# FPGA_7A35T_GTP.net
KiCad netlist of a schematic drawn in Altium Designer
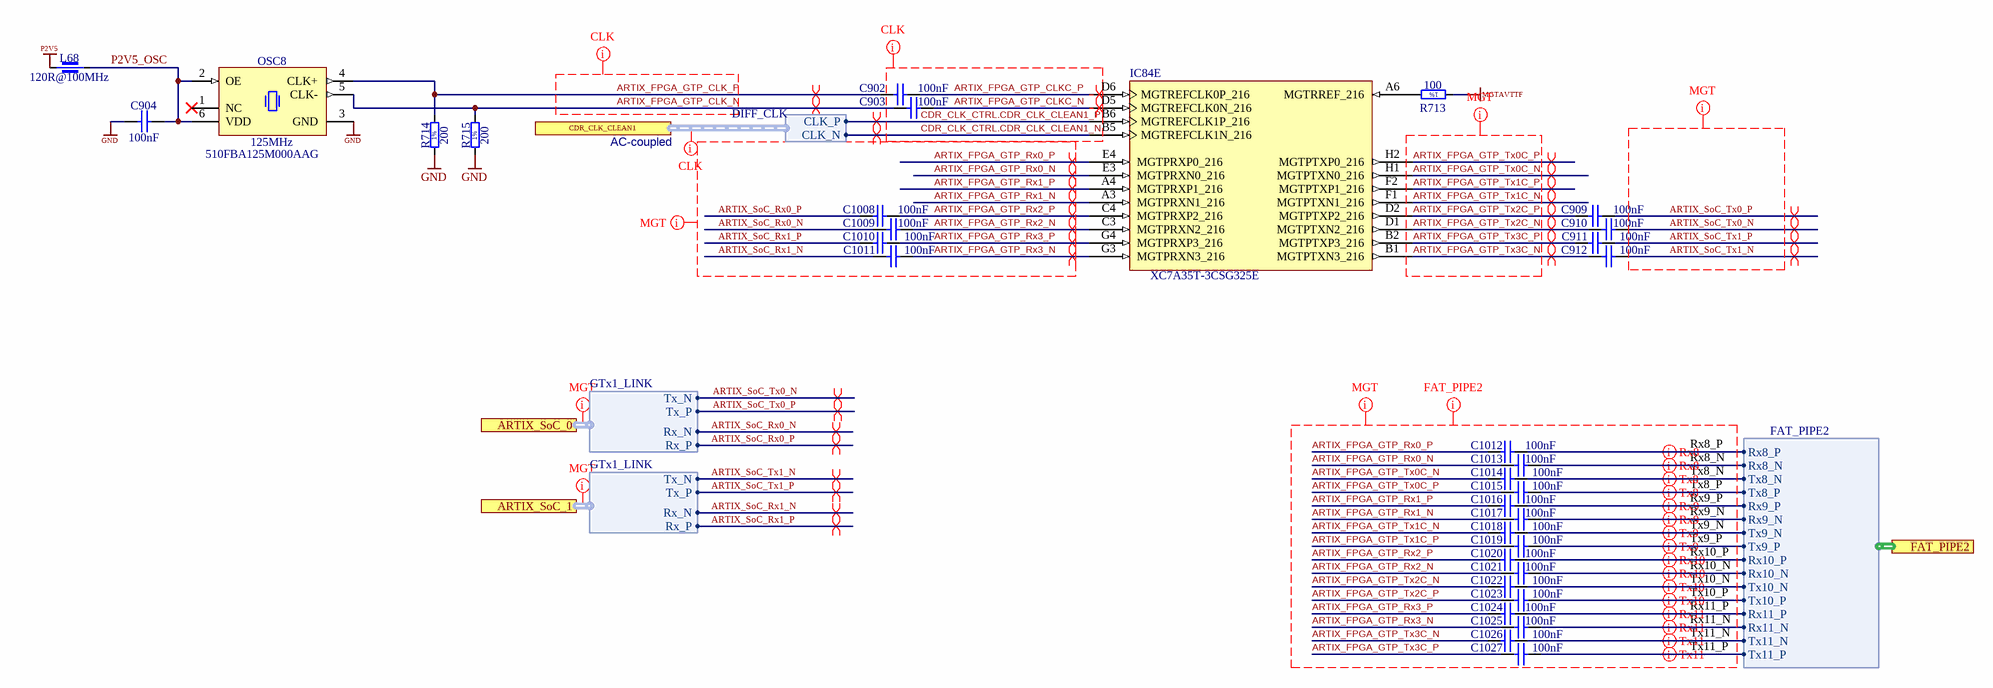
[diagram p0: FPGA_7A35T_GTP.SchDoc]

(export (version "E")
  (design (tool "Eeschema 10.0.6"))
  (components
    (comp (ref "C902")
      (value "100nF")
      (footprint "CAPC0603X33N")
      (description "Non-polarised capacitor")
      (fields
        (field (name "MANUFACTURER PART NUMBER") "CC0201_100NF_6.3V_10%_X5R")
        (field (name "MANUFACTURER") "GENERIC")
        (field (name "AUTHOR") "CERN DEM JLC")
      )
      (libsource (lib "Capacitors") (part "Capacitor - non polarized"))
    )
    (comp (ref "C903")
      (value "100nF")
      (footprint "CAPC0603X33N")
      (description "Non-polarised capacitor")
      (fields
        (field (name "MANUFACTURER PART NUMBER") "CC0201_100NF_6.3V_10%_X5R")
        (field (name "MANUFACTURER") "GENERIC")
        (field (name "AUTHOR") "CERN DEM JLC")
      )
      (libsource (lib "Capacitors") (part "Capacitor - non polarized"))
    )
    (comp (ref "C904")
      (value "100nF")
      (footprint "CAPC0603X33N")
      (description "Non-polarised capacitor")
      (fields
        (field (name "MANUFACTURER PART NUMBER") "CC0201_100NF_6.3V_10%_X5R")
        (field (name "MANUFACTURER") "GENERIC")
        (field (name "AUTHOR") "CERN DEM JLC")
      )
      (libsource (lib "Capacitors") (part "Capacitor - non polarized"))
    )
    (comp (ref "C909")
      (value "100nF")
      (footprint "CAPC0603X33N")
      (description "Non-polarised capacitor")
      (fields
        (field (name "MANUFACTURER PART NUMBER") "CC0201_100NF_6.3V_10%_X5R")
        (field (name "MANUFACTURER") "GENERIC")
        (field (name "AUTHOR") "CERN DEM JLC")
      )
      (libsource (lib "Capacitors") (part "Capacitor - non polarized"))
    )
    (comp (ref "C910")
      (value "100nF")
      (footprint "CAPC0603X33N")
      (description "Non-polarised capacitor")
      (fields
        (field (name "MANUFACTURER PART NUMBER") "CC0201_100NF_6.3V_10%_X5R")
        (field (name "MANUFACTURER") "GENERIC")
        (field (name "AUTHOR") "CERN DEM JLC")
      )
      (libsource (lib "Capacitors") (part "Capacitor - non polarized"))
    )
    (comp (ref "C911")
      (value "100nF")
      (footprint "CAPC0603X33N")
      (description "Non-polarised capacitor")
      (fields
        (field (name "MANUFACTURER PART NUMBER") "CC0201_100NF_6.3V_10%_X5R")
        (field (name "MANUFACTURER") "GENERIC")
        (field (name "AUTHOR") "CERN DEM JLC")
      )
      (libsource (lib "Capacitors") (part "Capacitor - non polarized"))
    )
    (comp (ref "C912")
      (value "100nF")
      (footprint "CAPC0603X33N")
      (description "Non-polarised capacitor")
      (fields
        (field (name "MANUFACTURER PART NUMBER") "CC0201_100NF_6.3V_10%_X5R")
        (field (name "MANUFACTURER") "GENERIC")
        (field (name "AUTHOR") "CERN DEM JLC")
      )
      (libsource (lib "Capacitors") (part "Capacitor - non polarized"))
    )
    (comp (ref "C1008")
      (value "100nF")
      (footprint "CAPC0603X33N")
      (description "Non-polarised capacitor")
      (fields
        (field (name "MANUFACTURER PART NUMBER") "CC0201_100NF_6.3V_10%_X5R")
        (field (name "MANUFACTURER") "GENERIC")
        (field (name "AUTHOR") "CERN DEM JLC")
      )
      (libsource (lib "Capacitors") (part "Capacitor - non polarized"))
    )
    (comp (ref "C1009")
      (value "100nF")
      (footprint "CAPC0603X33N")
      (description "Non-polarised capacitor")
      (fields
        (field (name "MANUFACTURER PART NUMBER") "CC0201_100NF_6.3V_10%_X5R")
        (field (name "MANUFACTURER") "GENERIC")
        (field (name "AUTHOR") "CERN DEM JLC")
      )
      (libsource (lib "Capacitors") (part "Capacitor - non polarized"))
    )
    (comp (ref "C1010")
      (value "100nF")
      (footprint "CAPC0603X33N")
      (description "Non-polarised capacitor")
      (fields
        (field (name "MANUFACTURER PART NUMBER") "CC0201_100NF_6.3V_10%_X5R")
        (field (name "MANUFACTURER") "GENERIC")
        (field (name "AUTHOR") "CERN DEM JLC")
      )
      (libsource (lib "Capacitors") (part "Capacitor - non polarized"))
    )
    (comp (ref "C1011")
      (value "100nF")
      (footprint "CAPC0603X33N")
      (description "Non-polarised capacitor")
      (fields
        (field (name "MANUFACTURER PART NUMBER") "CC0201_100NF_6.3V_10%_X5R")
        (field (name "MANUFACTURER") "GENERIC")
        (field (name "AUTHOR") "CERN DEM JLC")
      )
      (libsource (lib "Capacitors") (part "Capacitor - non polarized"))
    )
    (comp (ref "C1012")
      (value "100nF")
      (footprint "CAPC0603X33N")
      (description "Non-polarised capacitor")
      (fields
        (field (name "MANUFACTURER PART NUMBER") "CC0201_100NF_6.3V_10%_X5R")
        (field (name "MANUFACTURER") "GENERIC")
        (field (name "AUTHOR") "CERN DEM JLC")
      )
      (libsource (lib "Capacitors") (part "Capacitor - non polarized"))
    )
    (comp (ref "C1013")
      (value "100nF")
      (footprint "CAPC0603X33N")
      (description "Non-polarised capacitor")
      (fields
        (field (name "MANUFACTURER PART NUMBER") "CC0201_100NF_6.3V_10%_X5R")
        (field (name "MANUFACTURER") "GENERIC")
        (field (name "AUTHOR") "CERN DEM JLC")
      )
      (libsource (lib "Capacitors") (part "Capacitor - non polarized"))
    )
    (comp (ref "C1014")
      (value "100nF")
      (footprint "CAPC0603X33N")
      (description "Non-polarised capacitor")
      (fields
        (field (name "MANUFACTURER PART NUMBER") "CC0201_100NF_6.3V_10%_X5R")
        (field (name "MANUFACTURER") "GENERIC")
        (field (name "AUTHOR") "CERN DEM JLC")
      )
      (libsource (lib "Capacitors") (part "Capacitor - non polarized"))
    )
    (comp (ref "C1015")
      (value "100nF")
      (footprint "CAPC0603X33N")
      (description "Non-polarised capacitor")
      (fields
        (field (name "MANUFACTURER PART NUMBER") "CC0201_100NF_6.3V_10%_X5R")
        (field (name "MANUFACTURER") "GENERIC")
        (field (name "AUTHOR") "CERN DEM JLC")
      )
      (libsource (lib "Capacitors") (part "Capacitor - non polarized"))
    )
    (comp (ref "C1016")
      (value "100nF")
      (footprint "CAPC0603X33N")
      (description "Non-polarised capacitor")
      (fields
        (field (name "MANUFACTURER PART NUMBER") "CC0201_100NF_6.3V_10%_X5R")
        (field (name "MANUFACTURER") "GENERIC")
        (field (name "AUTHOR") "CERN DEM JLC")
      )
      (libsource (lib "Capacitors") (part "Capacitor - non polarized"))
    )
    (comp (ref "C1017")
      (value "100nF")
      (footprint "CAPC0603X33N")
      (description "Non-polarised capacitor")
      (fields
        (field (name "MANUFACTURER PART NUMBER") "CC0201_100NF_6.3V_10%_X5R")
        (field (name "MANUFACTURER") "GENERIC")
        (field (name "AUTHOR") "CERN DEM JLC")
      )
      (libsource (lib "Capacitors") (part "Capacitor - non polarized"))
    )
    (comp (ref "C1018")
      (value "100nF")
      (footprint "CAPC0603X33N")
      (description "Non-polarised capacitor")
      (fields
        (field (name "MANUFACTURER PART NUMBER") "CC0201_100NF_6.3V_10%_X5R")
        (field (name "MANUFACTURER") "GENERIC")
        (field (name "AUTHOR") "CERN DEM JLC")
      )
      (libsource (lib "Capacitors") (part "Capacitor - non polarized"))
    )
    (comp (ref "C1019")
      (value "100nF")
      (footprint "CAPC0603X33N")
      (description "Non-polarised capacitor")
      (fields
        (field (name "MANUFACTURER PART NUMBER") "CC0201_100NF_6.3V_10%_X5R")
        (field (name "MANUFACTURER") "GENERIC")
        (field (name "AUTHOR") "CERN DEM JLC")
      )
      (libsource (lib "Capacitors") (part "Capacitor - non polarized"))
    )
    (comp (ref "C1020")
      (value "100nF")
      (footprint "CAPC0603X33N")
      (description "Non-polarised capacitor")
      (fields
        (field (name "MANUFACTURER PART NUMBER") "CC0201_100NF_6.3V_10%_X5R")
        (field (name "MANUFACTURER") "GENERIC")
        (field (name "AUTHOR") "CERN DEM JLC")
      )
      (libsource (lib "Capacitors") (part "Capacitor - non polarized"))
    )
    (comp (ref "C1021")
      (value "100nF")
      (footprint "CAPC0603X33N")
      (description "Non-polarised capacitor")
      (fields
        (field (name "MANUFACTURER PART NUMBER") "CC0201_100NF_6.3V_10%_X5R")
        (field (name "MANUFACTURER") "GENERIC")
        (field (name "AUTHOR") "CERN DEM JLC")
      )
      (libsource (lib "Capacitors") (part "Capacitor - non polarized"))
    )
    (comp (ref "C1022")
      (value "100nF")
      (footprint "CAPC0603X33N")
      (description "Non-polarised capacitor")
      (fields
        (field (name "MANUFACTURER PART NUMBER") "CC0201_100NF_6.3V_10%_X5R")
        (field (name "MANUFACTURER") "GENERIC")
        (field (name "AUTHOR") "CERN DEM JLC")
      )
      (libsource (lib "Capacitors") (part "Capacitor - non polarized"))
    )
    (comp (ref "C1023")
      (value "100nF")
      (footprint "CAPC0603X33N")
      (description "Non-polarised capacitor")
      (fields
        (field (name "MANUFACTURER PART NUMBER") "CC0201_100NF_6.3V_10%_X5R")
        (field (name "MANUFACTURER") "GENERIC")
        (field (name "AUTHOR") "CERN DEM JLC")
      )
      (libsource (lib "Capacitors") (part "Capacitor - non polarized"))
    )
    (comp (ref "C1024")
      (value "100nF")
      (footprint "CAPC0603X33N")
      (description "Non-polarised capacitor")
      (fields
        (field (name "MANUFACTURER PART NUMBER") "CC0201_100NF_6.3V_10%_X5R")
        (field (name "MANUFACTURER") "GENERIC")
        (field (name "AUTHOR") "CERN DEM JLC")
      )
      (libsource (lib "Capacitors") (part "Capacitor - non polarized"))
    )
    (comp (ref "C1025")
      (value "100nF")
      (footprint "CAPC0603X33N")
      (description "Non-polarised capacitor")
      (fields
        (field (name "MANUFACTURER PART NUMBER") "CC0201_100NF_6.3V_10%_X5R")
        (field (name "MANUFACTURER") "GENERIC")
        (field (name "AUTHOR") "CERN DEM JLC")
      )
      (libsource (lib "Capacitors") (part "Capacitor - non polarized"))
    )
    (comp (ref "C1026")
      (value "100nF")
      (footprint "CAPC0603X33N")
      (description "Non-polarised capacitor")
      (fields
        (field (name "MANUFACTURER PART NUMBER") "CC0201_100NF_6.3V_10%_X5R")
        (field (name "MANUFACTURER") "GENERIC")
        (field (name "AUTHOR") "CERN DEM JLC")
      )
      (libsource (lib "Capacitors") (part "Capacitor - non polarized"))
    )
    (comp (ref "C1027")
      (value "100nF")
      (footprint "CAPC0603X33N")
      (description "Non-polarised capacitor")
      (fields
        (field (name "MANUFACTURER PART NUMBER") "CC0201_100NF_6.3V_10%_X5R")
        (field (name "MANUFACTURER") "GENERIC")
        (field (name "AUTHOR") "CERN DEM JLC")
      )
      (libsource (lib "Capacitors") (part "Capacitor - non polarized"))
    )
    (comp (ref "IC84")
      (value "XC7A35T-3CSG325E")
      (footprint "CSG325")
      (description "Artix-7 FPGA, 150 User I/Os, 4 GTP, 324-Ball BGA, Speed Grade 3, Extended Grade, Pb-Free")
      (fields (field (name "MANUFACTURER") "Xilinx"))
      (libsource (lib "Altium Content Vault") (part "XLNX-XC7A35T-CSG325"))
    )
    (comp (ref "L68")
      (value "120R@100MHz")
      (footprint "INDC1005X55N")
      (fields
        (field (name "MANUFACTURER PART NUMBER") "BLM15PX121SN1D")
        (field (name "MANUFACTURER") "MURATA")
        (field (name "PART NUMBER") "IND0402_MURATA_BLM15PX121SN1D")
        (field (name "AUTHOR") "CERN DEM JMW")
      )
      (libsource (lib "Inductors & Transformers") (part "Ferrite Bead"))
    )
    (comp (ref "OSC8")
      (value "125MHz")
      (footprint "OSC_SILICON-LAB_SI510-6N(5X7)")
      (description "Crystal Oscillator 6 pins, Si510 (LVDS/LVPECL/HCSL/Dual CMOS)")
      (fields
        (field (name "PART NUMBER") "OSC_125MHZ_SILICON-LAB_510FBA125M000AAG")
        (field (name "MANUFACTURER") "SILICON LABS")
        (field (name "MANUFACTURER PART NUMBER") "510FBA125M000AAG")
        (field (name "AUTHOR") "CERN DEM JMW")
      )
      (libsource (lib "ICs And Semiconductors") (part "Oscillator SILICON-LAB_Si510-6N"))
    )
    (comp (ref "R713")
      (value "100")
      (footprint "RESC1005X40N")
      (description "Resistor - 1%")
      (fields
        (field (name "MANUFACTURER PART NUMBER") "R0402_100R_1%_0.0625W_100PPM")
        (field (name "MANUFACTURER") "GENERIC")
        (field (name "AUTHOR") "CERN DEM JLC")
      )
      (libsource (lib "Resistors") (part "Resistor - 1%"))
    )
    (comp (ref "R714")
      (value "200")
      (footprint "RESC1005X40N")
      (description "Resistor - 1%")
      (fields
        (field (name "MANUFACTURER PART NUMBER") "R0402_200R_1%_0.0625W_100PPM")
        (field (name "MANUFACTURER") "GENERIC")
        (field (name "AUTHOR") "CERN DEM JLC")
      )
      (libsource (lib "Resistors") (part "Resistor - 1%"))
    )
    (comp (ref "R715")
      (value "200")
      (footprint "RESC1005X40N")
      (description "Resistor - 1%")
      (fields
        (field (name "MANUFACTURER PART NUMBER") "R0402_200R_1%_0.0625W_100PPM")
        (field (name "MANUFACTURER") "GENERIC")
        (field (name "AUTHOR") "CERN DEM JLC")
      )
      (libsource (lib "Resistors") (part "Resistor - 1%"))
    )
  )
  (nets
    (net (code "4") (name "/ARTIX_FPGA_GTP_CLKC_N") (class "Default")
      (node (ref "C903") (pin "2") (pinfunction "2_2") (pintype "passive"))
      (node (ref "IC84") (pin "D5") (pinfunction "MGTREFCLK0N_216_D5") (pintype "input"))
    )
    (net (code "5") (name "/ARTIX_FPGA_GTP_CLKC_P") (class "Default")
      (node (ref "C902") (pin "2") (pinfunction "2_2") (pintype "passive"))
      (node (ref "IC84") (pin "D6") (pinfunction "MGTREFCLK0P_216_D6") (pintype "input"))
    )
    (net (code "6") (name "/ARTIX_FPGA_GTP_CLK_N") (class "Default")
      (node (ref "C903") (pin "1") (pinfunction "1_1") (pintype "passive"))
      (node (ref "OSC8") (pin "5") (pinfunction "CLK-_5") (pintype "output"))
      (node (ref "R715") (pin "2") (pinfunction "2_2") (pintype "passive"))
    )
    (net (code "7") (name "/ARTIX_FPGA_GTP_CLK_P") (class "Default")
      (node (ref "C902") (pin "1") (pinfunction "1_1") (pintype "passive"))
      (node (ref "OSC8") (pin "4") (pinfunction "CLK+_4") (pintype "output"))
      (node (ref "R714") (pin "2") (pinfunction "2_2") (pintype "passive"))
    )
    (net (code "8") (name "/ARTIX_FPGA_GTP_Rx0_N") (class "Default")
      (node (ref "C1013") (pin "2") (pinfunction "2_2") (pintype "passive"))
      (node (ref "IC84") (pin "E3") (pinfunction "MGTPRXN0_216_E3") (pintype "input"))
    )
    (net (code "9") (name "/ARTIX_FPGA_GTP_Rx0_P") (class "Default")
      (node (ref "C1012") (pin "2") (pinfunction "2_2") (pintype "passive"))
      (node (ref "IC84") (pin "E4") (pinfunction "MGTPRXP0_216_E4") (pintype "input"))
    )
    (net (code "10") (name "/ARTIX_FPGA_GTP_Rx1_N") (class "Default")
      (node (ref "C1017") (pin "2") (pinfunction "2_2") (pintype "passive"))
      (node (ref "IC84") (pin "A3") (pinfunction "MGTPRXN1_216_A3") (pintype "input"))
    )
    (net (code "11") (name "/ARTIX_FPGA_GTP_Rx1_P") (class "Default")
      (node (ref "C1016") (pin "2") (pinfunction "2_2") (pintype "passive"))
      (node (ref "IC84") (pin "A4") (pinfunction "MGTPRXP1_216_A4") (pintype "input"))
    )
    (net (code "12") (name "/ARTIX_FPGA_GTP_Rx2_N") (class "Default")
      (node (ref "C1009") (pin "1") (pinfunction "1_1") (pintype "passive"))
      (node (ref "C1021") (pin "2") (pinfunction "2_2") (pintype "passive"))
      (node (ref "IC84") (pin "C3") (pinfunction "MGTPRXN2_216_C3") (pintype "input"))
    )
    (net (code "13") (name "/ARTIX_FPGA_GTP_Rx2_P") (class "Default")
      (node (ref "C1008") (pin "1") (pinfunction "1_1") (pintype "passive"))
      (node (ref "C1020") (pin "2") (pinfunction "2_2") (pintype "passive"))
      (node (ref "IC84") (pin "C4") (pinfunction "MGTPRXP2_216_C4") (pintype "input"))
    )
    (net (code "14") (name "/ARTIX_FPGA_GTP_Rx3_N") (class "Default")
      (node (ref "C1011") (pin "1") (pinfunction "1_1") (pintype "passive"))
      (node (ref "C1025") (pin "2") (pinfunction "2_2") (pintype "passive"))
      (node (ref "IC84") (pin "G3") (pinfunction "MGTPRXN3_216_G3") (pintype "input"))
    )
    (net (code "15") (name "/ARTIX_FPGA_GTP_Rx3_P") (class "Default")
      (node (ref "C1010") (pin "1") (pinfunction "1_1") (pintype "passive"))
      (node (ref "C1024") (pin "2") (pinfunction "2_2") (pintype "passive"))
      (node (ref "IC84") (pin "G4") (pinfunction "MGTPRXP3_216_G4") (pintype "input"))
    )
    (net (code "16") (name "/ARTIX_FPGA_GTP_Tx0C_N") (class "Default")
      (node (ref "C1014") (pin "2") (pinfunction "2_2") (pintype "passive"))
      (node (ref "IC84") (pin "H1") (pinfunction "MGTPTXN0_216_H1") (pintype "output"))
    )
    (net (code "17") (name "/ARTIX_FPGA_GTP_Tx0C_P") (class "Default")
      (node (ref "C1015") (pin "2") (pinfunction "2_2") (pintype "passive"))
      (node (ref "IC84") (pin "H2") (pinfunction "MGTPTXP0_216_H2") (pintype "output"))
    )
    (net (code "18") (name "/ARTIX_FPGA_GTP_Tx1C_N") (class "Default")
      (node (ref "C1018") (pin "2") (pinfunction "2_2") (pintype "passive"))
      (node (ref "IC84") (pin "F1") (pinfunction "MGTPTXN1_216_F1") (pintype "output"))
    )
    (net (code "19") (name "/ARTIX_FPGA_GTP_Tx1C_P") (class "Default")
      (node (ref "C1019") (pin "2") (pinfunction "2_2") (pintype "passive"))
      (node (ref "IC84") (pin "F2") (pinfunction "MGTPTXP1_216_F2") (pintype "output"))
    )
    (net (code "20") (name "/ARTIX_FPGA_GTP_Tx2C_N") (class "Default")
      (node (ref "C1022") (pin "2") (pinfunction "2_2") (pintype "passive"))
      (node (ref "C910") (pin "2") (pinfunction "2_2") (pintype "passive"))
      (node (ref "IC84") (pin "D1") (pinfunction "MGTPTXN2_216_D1") (pintype "output"))
    )
    (net (code "21") (name "/ARTIX_FPGA_GTP_Tx2C_P") (class "Default")
      (node (ref "C1023") (pin "2") (pinfunction "2_2") (pintype "passive"))
      (node (ref "C909") (pin "2") (pinfunction "2_2") (pintype "passive"))
      (node (ref "IC84") (pin "D2") (pinfunction "MGTPTXP2_216_D2") (pintype "output"))
    )
    (net (code "22") (name "/ARTIX_FPGA_GTP_Tx3C_N") (class "Default")
      (node (ref "C1026") (pin "2") (pinfunction "2_2") (pintype "passive"))
      (node (ref "C912") (pin "2") (pinfunction "2_2") (pintype "passive"))
      (node (ref "IC84") (pin "B1") (pinfunction "MGTPTXN3_216_B1") (pintype "output"))
    )
    (net (code "23") (name "/ARTIX_FPGA_GTP_Tx3C_P") (class "Default")
      (node (ref "C1027") (pin "2") (pinfunction "2_2") (pintype "passive"))
      (node (ref "C911") (pin "2") (pinfunction "2_2") (pintype "passive"))
      (node (ref "IC84") (pin "B2") (pinfunction "MGTPTXP3_216_B2") (pintype "output"))
    )
    (net (code "24") (name "/ARTIX_SoC_Rx0_N") (class "Default")
      (node (ref "C1009") (pin "2") (pinfunction "2_2") (pintype "passive"))
    )
    (net (code "25") (name "/ARTIX_SoC_Rx0_P") (class "Default")
      (node (ref "C1008") (pin "2") (pinfunction "2_2") (pintype "passive"))
    )
    (net (code "26") (name "/ARTIX_SoC_Rx1_N") (class "Default")
      (node (ref "C1011") (pin "2") (pinfunction "2_2") (pintype "passive"))
    )
    (net (code "27") (name "/ARTIX_SoC_Rx1_P") (class "Default")
      (node (ref "C1010") (pin "2") (pinfunction "2_2") (pintype "passive"))
    )
    (net (code "28") (name "/ARTIX_SoC_Tx0_N") (class "Default")
      (node (ref "C910") (pin "1") (pinfunction "1_1") (pintype "passive"))
    )
    (net (code "29") (name "/ARTIX_SoC_Tx0_P") (class "Default")
      (node (ref "C909") (pin "1") (pinfunction "1_1") (pintype "passive"))
    )
    (net (code "30") (name "/ARTIX_SoC_Tx1_N") (class "Default")
      (node (ref "C912") (pin "1") (pinfunction "1_1") (pintype "passive"))
    )
    (net (code "31") (name "/ARTIX_SoC_Tx1_P") (class "Default")
      (node (ref "C911") (pin "1") (pinfunction "1_1") (pintype "passive"))
    )
    (net (code "32") (name "/CDR_CLK_CTRL.CDR_CLK_CLEAN1_N") (class "Default")
      (node (ref "IC84") (pin "B5") (pinfunction "MGTREFCLK1N_216_B5") (pintype "input"))
    )
    (net (code "33") (name "/CDR_CLK_CTRL.CDR_CLK_CLEAN1_P") (class "Default")
      (node (ref "IC84") (pin "B6") (pinfunction "MGTREFCLK1P_216_B6") (pintype "input"))
    )
    (net (code "34") (name "/P2V5_OSC") (class "Default")
      (node (ref "C904") (pin "2") (pinfunction "2_2") (pintype "passive"))
      (node (ref "L68") (pin "1") (pinfunction "1_1") (pintype "passive"))
      (node (ref "OSC8") (pin "2") (pinfunction "OE_2") (pintype "input"))
      (node (ref "OSC8") (pin "6") (pinfunction "VDD_6") (pintype "power_in"))
    )
    (net (code "35") (name "/Rx8_N") (class "Default")
      (node (ref "C1013") (pin "1") (pinfunction "1_1") (pintype "passive"))
    )
    (net (code "36") (name "/Rx8_P") (class "Default")
      (node (ref "C1012") (pin "1") (pinfunction "1_1") (pintype "passive"))
    )
    (net (code "37") (name "/Rx9_N") (class "Default")
      (node (ref "C1017") (pin "1") (pinfunction "1_1") (pintype "passive"))
    )
    (net (code "38") (name "/Rx9_P") (class "Default")
      (node (ref "C1016") (pin "1") (pinfunction "1_1") (pintype "passive"))
    )
    (net (code "39") (name "/Rx10_N") (class "Default")
      (node (ref "C1021") (pin "1") (pinfunction "1_1") (pintype "passive"))
    )
    (net (code "40") (name "/Rx10_P") (class "Default")
      (node (ref "C1020") (pin "1") (pinfunction "1_1") (pintype "passive"))
    )
    (net (code "41") (name "/Rx11_N") (class "Default")
      (node (ref "C1025") (pin "1") (pinfunction "1_1") (pintype "passive"))
    )
    (net (code "42") (name "/Rx11_P") (class "Default")
      (node (ref "C1024") (pin "1") (pinfunction "1_1") (pintype "passive"))
    )
    (net (code "43") (name "/Tx8_N") (class "Default")
      (node (ref "C1014") (pin "1") (pinfunction "1_1") (pintype "passive"))
    )
    (net (code "44") (name "/Tx8_P") (class "Default")
      (node (ref "C1015") (pin "1") (pinfunction "1_1") (pintype "passive"))
    )
    (net (code "45") (name "/Tx9_N") (class "Default")
      (node (ref "C1018") (pin "1") (pinfunction "1_1") (pintype "passive"))
    )
    (net (code "46") (name "/Tx9_P") (class "Default")
      (node (ref "C1019") (pin "1") (pinfunction "1_1") (pintype "passive"))
    )
    (net (code "47") (name "/Tx10_N") (class "Default")
      (node (ref "C1022") (pin "1") (pinfunction "1_1") (pintype "passive"))
    )
    (net (code "48") (name "/Tx10_P") (class "Default")
      (node (ref "C1023") (pin "1") (pinfunction "1_1") (pintype "passive"))
    )
    (net (code "49") (name "/Tx11_N") (class "Default")
      (node (ref "C1026") (pin "1") (pinfunction "1_1") (pintype "passive"))
    )
    (net (code "50") (name "/Tx11_P") (class "Default")
      (node (ref "C1027") (pin "1") (pinfunction "1_1") (pintype "passive"))
    )
    (net (code "54") (name "GND") (class "Default")
      (node (ref "C904") (pin "1") (pinfunction "1_1") (pintype "passive"))
      (node (ref "OSC8") (pin "3") (pinfunction "GND_3") (pintype "power_in"))
      (node (ref "R714") (pin "1") (pinfunction "1_1") (pintype "passive"))
      (node (ref "R715") (pin "1") (pinfunction "1_1") (pintype "passive"))
    )
    (net (code "55") (name "MGTAVTTF") (class "Default")
      (node (ref "R713") (pin "1") (pinfunction "1_1") (pintype "passive"))
    )
    (net (code "56") (name "Net-(IC84E-MGTRREF_216)") (class "Default")
      (node (ref "IC84") (pin "A6") (pinfunction "MGTRREF_216_A6") (pintype "input"))
      (node (ref "R713") (pin "2") (pinfunction "2_2") (pintype "passive"))
    )
    (net (code "57") (name "P2V5") (class "Default")
      (node (ref "L68") (pin "2") (pinfunction "2_2") (pintype "passive"))
    )
    (net (code "58") (name "unconnected-(OSC8-NC-Pad1)") (class "Default")
      (node (ref "OSC8") (pin "1") (pinfunction "NC_1") (pintype "passive+no_connect"))
    )
  )
)
